# TSOC_RS485_EM.net
KiCad netlist of a schematic drawn in EAGLE
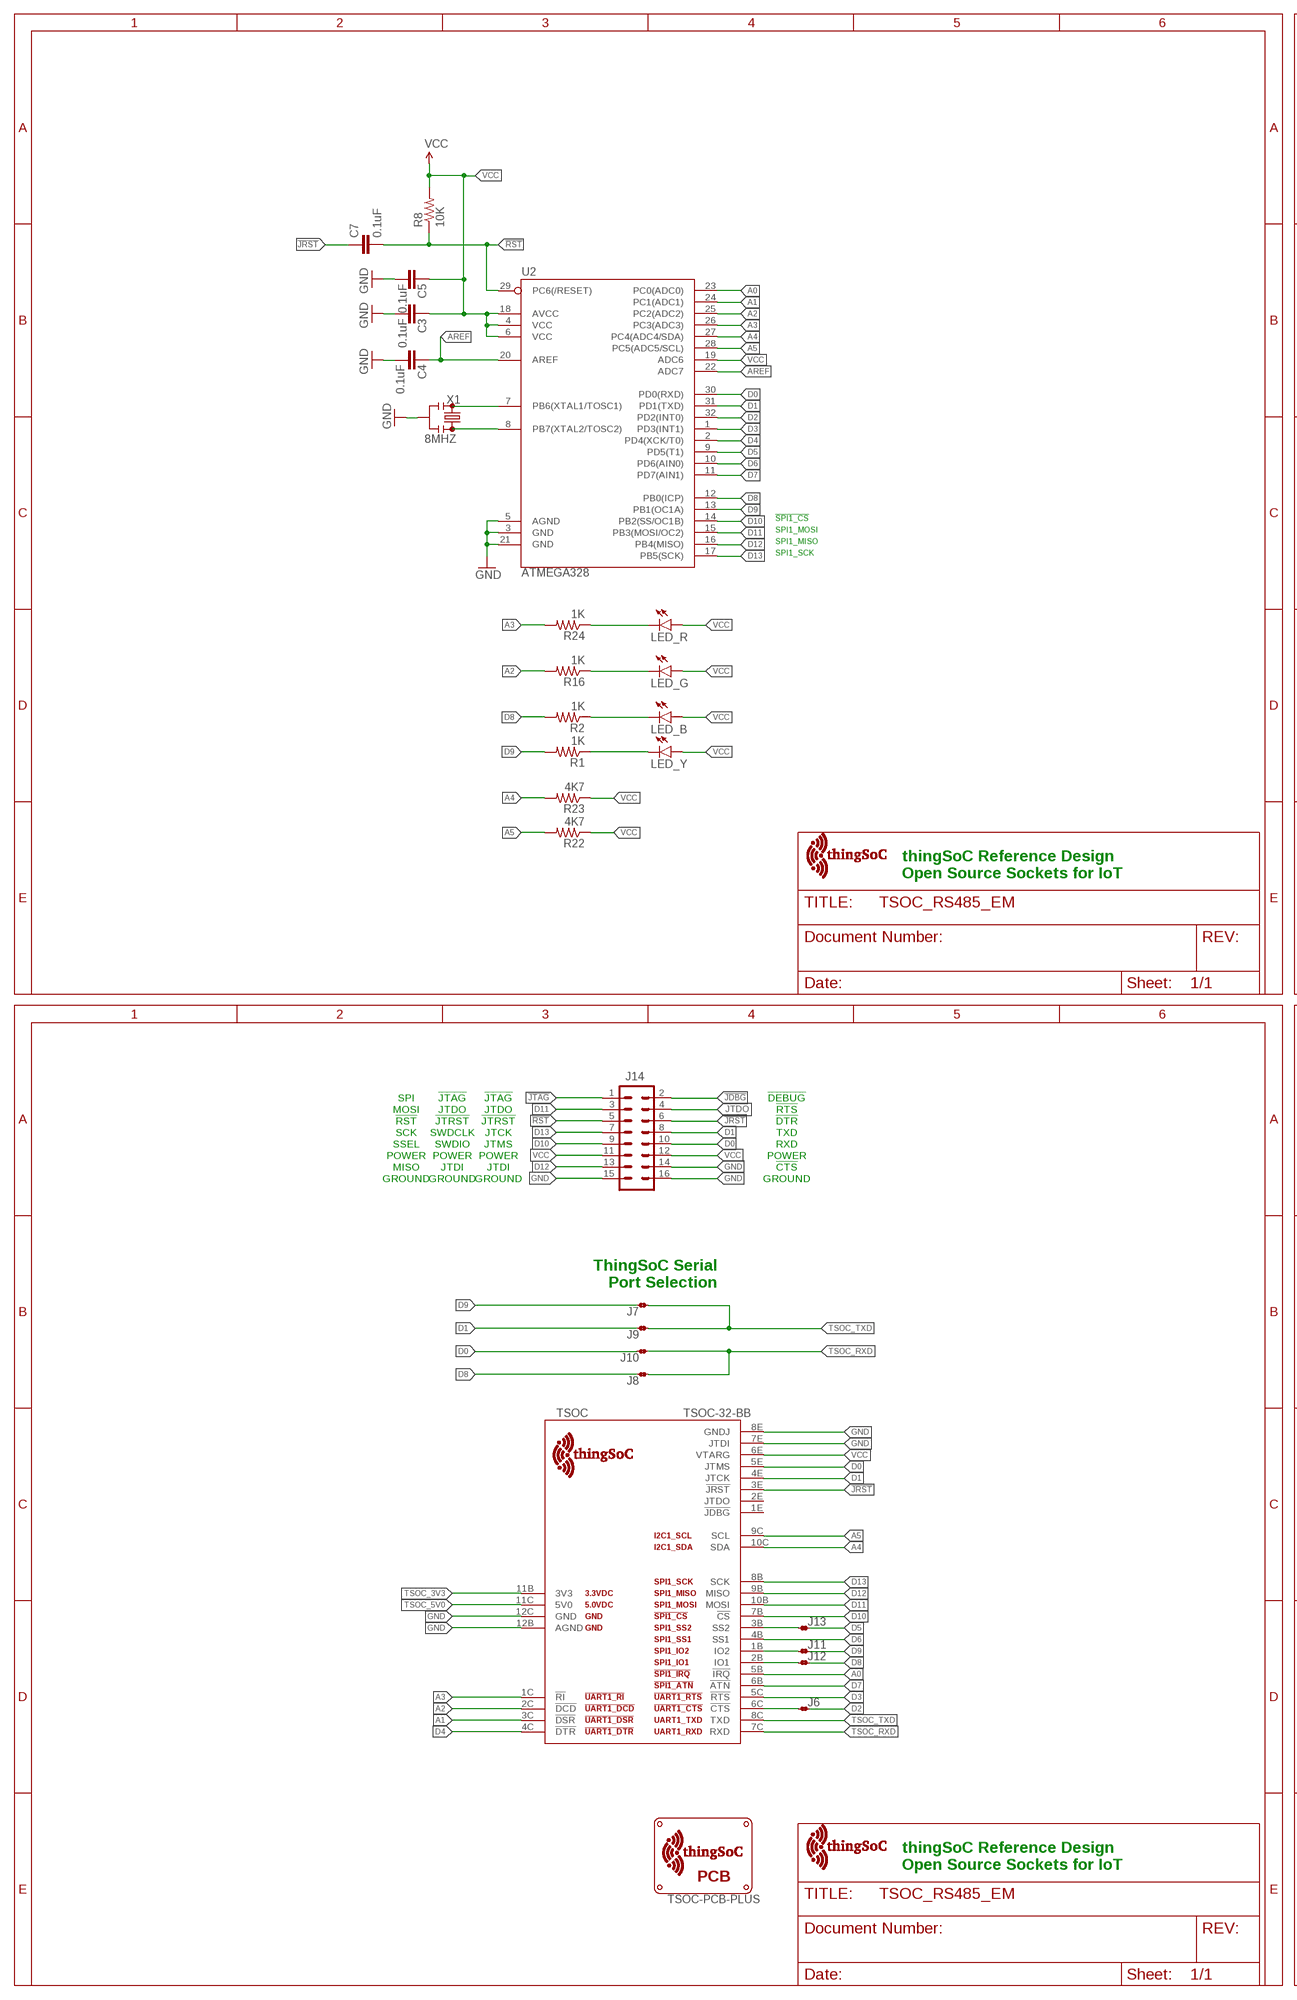
[diagram p0: schematic, sheet 1, part 1 of 2]
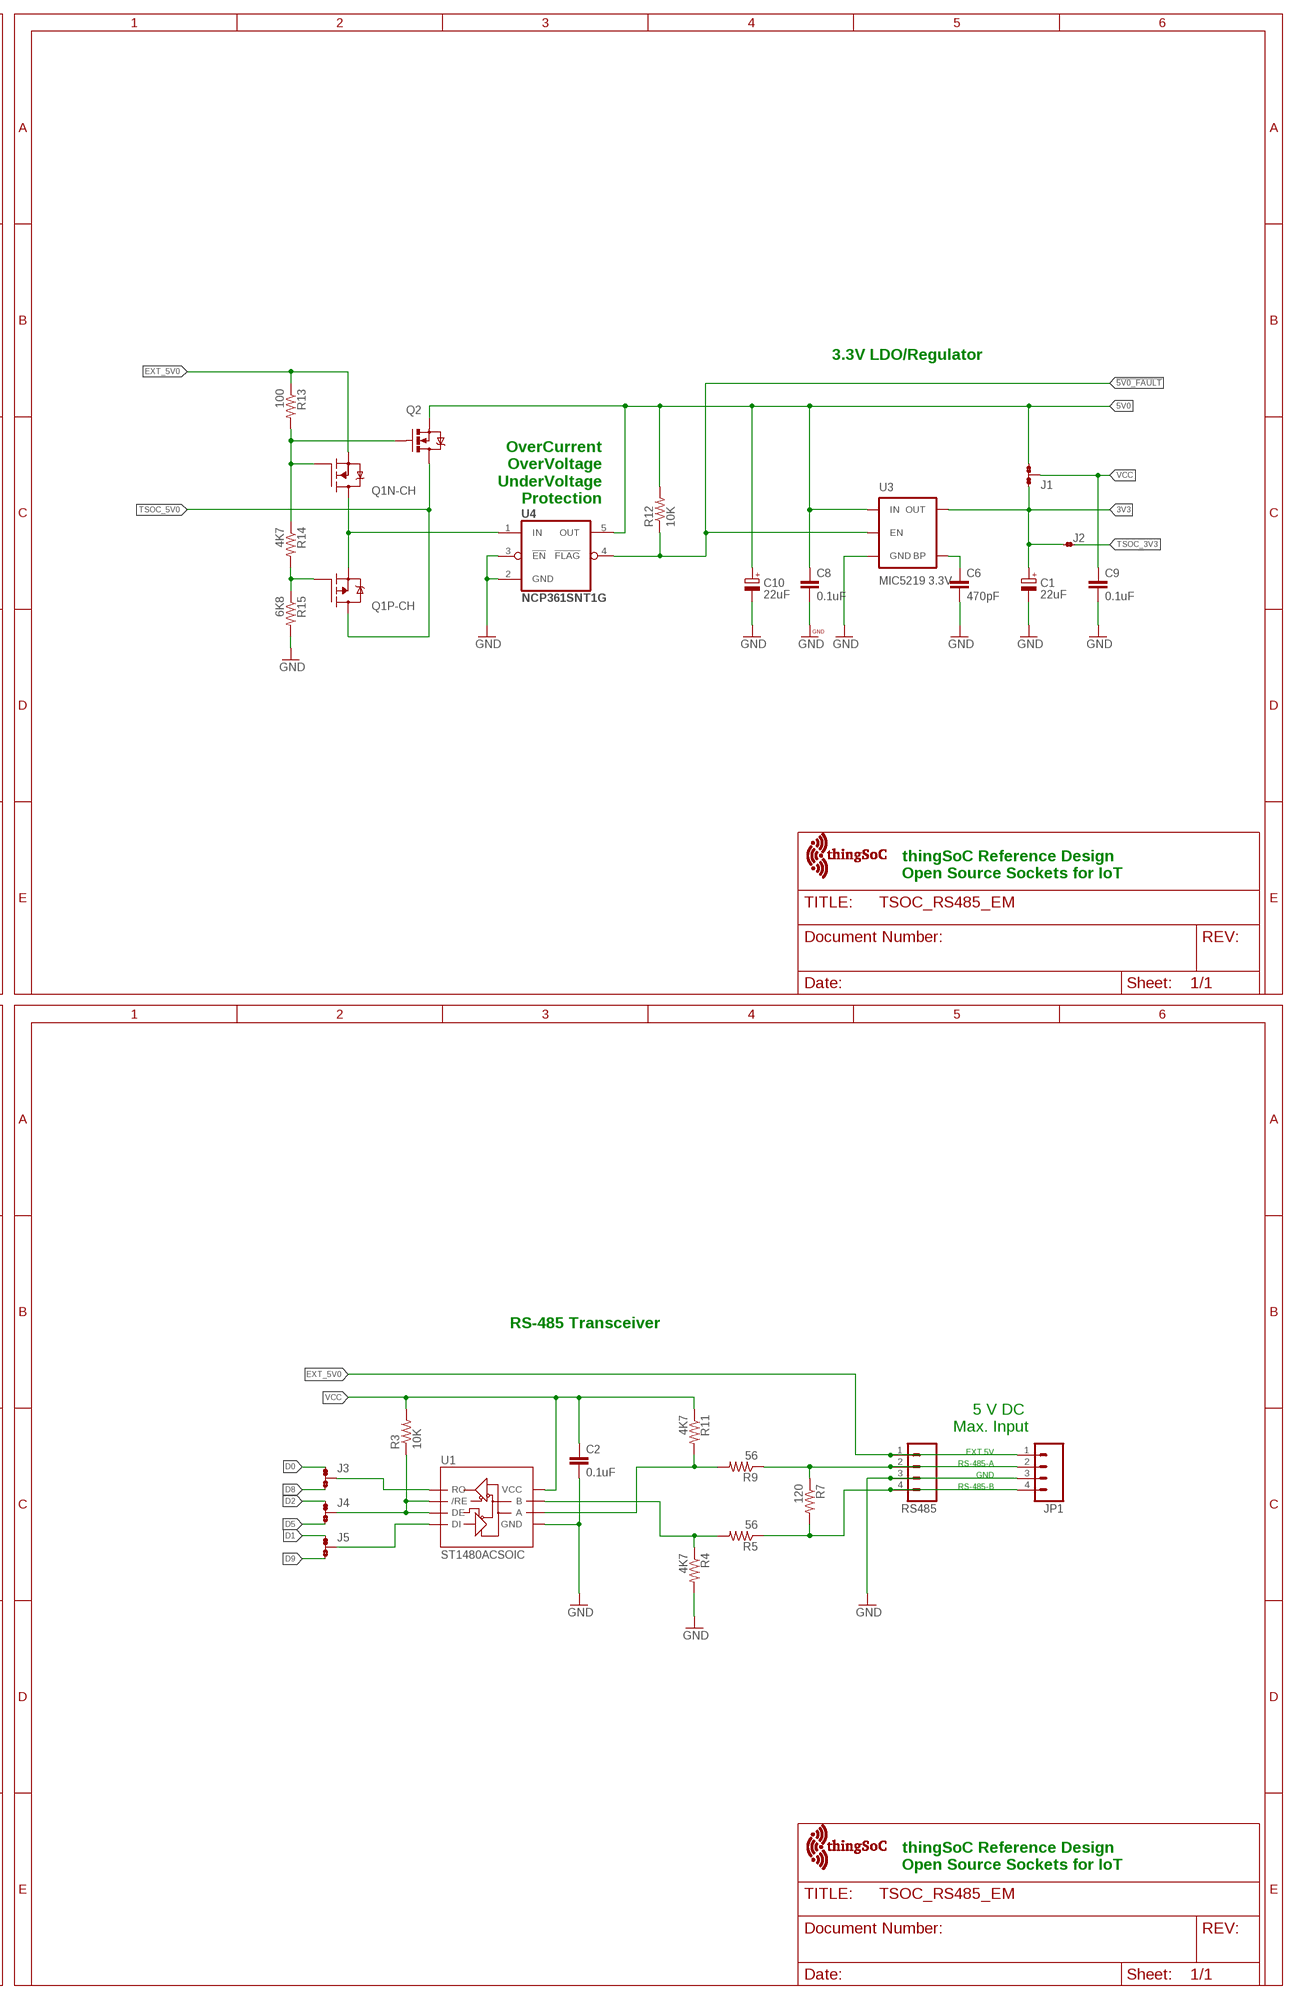
[diagram p1: schematic, sheet 1, part 2 of 2]

(export (version "E")
  (design (tool "Eeschema 10.0.6"))
  (components
    (comp (ref "C1")
      (value "22uF")
      (footprint "eagle-import:SMC_B")
      (libsource (lib "eagle-import") (part "CPOL-EUSMCB"))
    )
    (comp (ref "C2")
      (value "0.1uF")
      (footprint "eagle-import:EIA-0402")
      (libsource (lib "eagle-import") (part "CAPTYP"))
    )
    (comp (ref "C3")
      (value "0.1uF")
      (footprint "eagle-import:EIA-0402")
      (libsource (lib "eagle-import") (part "CAPTYP"))
    )
    (comp (ref "C4")
      (value "0.1uF")
      (footprint "eagle-import:EIA-0402")
      (libsource (lib "eagle-import") (part "CAPTYP"))
    )
    (comp (ref "C5")
      (value "0.1uF")
      (footprint "eagle-import:EIA-0402")
      (libsource (lib "eagle-import") (part "CAPTYP"))
    )
    (comp (ref "C6")
      (value "470pF")
      (footprint "eagle-import:EIA-0402")
      (libsource (lib "eagle-import") (part "CAPTYP"))
    )
    (comp (ref "C7")
      (value "0.1uF")
      (footprint "eagle-import:EIA-0402")
      (libsource (lib "eagle-import") (part "CAPTYP"))
    )
    (comp (ref "C8")
      (value "0.1uF")
      (footprint "eagle-import:EIA-0402")
      (libsource (lib "eagle-import") (part "CAPTYP"))
    )
    (comp (ref "C9")
      (value "0.1uF")
      (footprint "eagle-import:EIA-0402")
      (libsource (lib "eagle-import") (part "CAPTYP"))
    )
    (comp (ref "C10")
      (value "22uF")
      (footprint "eagle-import:SMC_B")
      (libsource (lib "eagle-import") (part "CPOL-EUSMCB"))
    )
    (comp (ref "J1")
      (value "JMP-3-1_2")
      (footprint "eagle-import:JMP-3-1_2")
      (libsource (lib "eagle-import") (part "JMP-3-1_2"))
    )
    (comp (ref "J2")
      (value "JMP-2-NC")
      (footprint "eagle-import:JMP-2-NC")
      (libsource (lib "eagle-import") (part "JMP-2-NC"))
    )
    (comp (ref "J3")
      (value "JMP-3-1_2")
      (footprint "eagle-import:JMP-3-1_2")
      (libsource (lib "eagle-import") (part "TSOC_RS485_EM_JMP-3-1_2"))
    )
    (comp (ref "J4")
      (value "JMP-3-1_2")
      (footprint "eagle-import:JMP-3-1_2")
      (libsource (lib "eagle-import") (part "TSOC_RS485_EM_JMP-3-1_2"))
    )
    (comp (ref "J5")
      (value "JMP-3-1_2")
      (footprint "eagle-import:JMP-3-1_2")
      (libsource (lib "eagle-import") (part "TSOC_RS485_EM_JMP-3-1_2"))
    )
    (comp (ref "J6")
      (value "JMP-2-NO")
      (footprint "eagle-import:JMP-2-NO")
      (libsource (lib "eagle-import") (part "JMP-2-NO"))
    )
    (comp (ref "J7")
      (value "JMP-2-NO")
      (footprint "eagle-import:JMP-2-NO")
      (libsource (lib "eagle-import") (part "JMP-2-NO"))
    )
    (comp (ref "J8")
      (value "JMP-2-NO")
      (footprint "eagle-import:JMP-2-NO")
      (libsource (lib "eagle-import") (part "JMP-2-NO"))
    )
    (comp (ref "J9")
      (value "JMP-2-NO")
      (footprint "eagle-import:JMP-2-NO")
      (libsource (lib "eagle-import") (part "JMP-2-NO"))
    )
    (comp (ref "J10")
      (value "JMP-2-NO")
      (footprint "eagle-import:JMP-2-NO")
      (libsource (lib "eagle-import") (part "JMP-2-NO"))
    )
    (comp (ref "J11")
      (value "JMP-2-NC")
      (footprint "eagle-import:JMP-2-NC")
      (libsource (lib "eagle-import") (part "JMP-2-NC"))
    )
    (comp (ref "J12")
      (value "JMP-2-NC")
      (footprint "eagle-import:JMP-2-NC")
      (libsource (lib "eagle-import") (part "JMP-2-NC"))
    )
    (comp (ref "J13")
      (value "JMP-2-NC")
      (footprint "eagle-import:JMP-2-NC")
      (libsource (lib "eagle-import") (part "JMP-2-NC"))
    )
    (comp (ref "J14")
      (value "M08X2")
      (footprint "eagle-import:2X8")
      (libsource (lib "eagle-import") (part "M08X2"))
    )
    (comp (ref "JP1")
      (value "M04PTH")
      (footprint "eagle-import:1X04")
      (libsource (lib "eagle-import") (part "M04PTH"))
    )
    (comp (ref "LED_B")
      (value "LED0603")
      (footprint "eagle-import:LED-0603")
      (libsource (lib "eagle-import") (part "LED0603"))
    )
    (comp (ref "LED_G")
      (value "LED0603")
      (footprint "eagle-import:LED-0603")
      (libsource (lib "eagle-import") (part "LED0603"))
    )
    (comp (ref "LED_R")
      (value "LED0603")
      (footprint "eagle-import:LED-0603")
      (libsource (lib "eagle-import") (part "LED0603"))
    )
    (comp (ref "LED_Y")
      (value "LED0603")
      (footprint "eagle-import:LED-0603")
      (libsource (lib "eagle-import") (part "LED0603"))
    )
    (comp (ref "Q1")
      (value "FDC6420C")
      (footprint "eagle-import:SOT95P280X110-6N")
      (libsource (lib "eagle-import") (part "FDC6420C"))
    )
    (comp (ref "Q2")
      (value "MOSFET-NCHANNELAO3404A")
      (footprint "eagle-import:SOT23-3")
      (libsource (lib "eagle-import") (part "MOSFET-NCHANNELAO3404A"))
    )
    (comp (ref "R1")
      (value "1K")
      (footprint "eagle-import:EIA-0402-MIN")
      (libsource (lib "eagle-import") (part "RESISTOR0402-MIN"))
    )
    (comp (ref "R2")
      (value "1K")
      (footprint "eagle-import:EIA-0402-MIN")
      (libsource (lib "eagle-import") (part "RESISTOR0402-MIN"))
    )
    (comp (ref "R3")
      (value "10K")
      (footprint "eagle-import:EIA-0402-MIN")
      (libsource (lib "eagle-import") (part "RESISTOR0402-MIN"))
    )
    (comp (ref "R4")
      (value "4K7")
      (footprint "eagle-import:EIA-0402-MIN")
      (libsource (lib "eagle-import") (part "RESISTOR0402-MIN"))
    )
    (comp (ref "R5")
      (value "56")
      (footprint "eagle-import:EIA-0402-MIN")
      (libsource (lib "eagle-import") (part "RESISTOR0402-MIN"))
    )
    (comp (ref "R7")
      (value "120")
      (footprint "eagle-import:EIA-0402-MIN")
      (libsource (lib "eagle-import") (part "RESISTOR0402-MIN"))
    )
    (comp (ref "R8")
      (value "10K")
      (footprint "eagle-import:EIA-0402-MIN")
      (libsource (lib "eagle-import") (part "RESISTOR0402-MIN"))
    )
    (comp (ref "R9")
      (value "56")
      (footprint "eagle-import:EIA-0402-MIN")
      (libsource (lib "eagle-import") (part "RESISTOR0402-MIN"))
    )
    (comp (ref "R11")
      (value "4K7")
      (footprint "eagle-import:EIA-0402-MIN")
      (libsource (lib "eagle-import") (part "RESISTOR0402-MIN"))
    )
    (comp (ref "R12")
      (value "10K")
      (footprint "eagle-import:EIA-0402-MIN")
      (libsource (lib "eagle-import") (part "RESISTOR0402-MIN"))
    )
    (comp (ref "R13")
      (value "100")
      (footprint "eagle-import:EIA-0402-MIN")
      (libsource (lib "eagle-import") (part "RESISTOR0402-MIN"))
    )
    (comp (ref "R14")
      (value "4K7")
      (footprint "eagle-import:EIA-0402-MIN")
      (libsource (lib "eagle-import") (part "RESISTOR0402-MIN"))
    )
    (comp (ref "R15")
      (value "6K8")
      (footprint "eagle-import:EIA-0402-MIN")
      (libsource (lib "eagle-import") (part "RESISTOR0402-MIN"))
    )
    (comp (ref "R16")
      (value "1K")
      (footprint "eagle-import:EIA-0402-MIN")
      (libsource (lib "eagle-import") (part "RESISTOR0402-MIN"))
    )
    (comp (ref "R22")
      (value "4K7")
      (footprint "eagle-import:EIA-0402-MIN")
      (libsource (lib "eagle-import") (part "RESISTOR0402-MIN"))
    )
    (comp (ref "R23")
      (value "4K7")
      (footprint "eagle-import:EIA-0402-MIN")
      (libsource (lib "eagle-import") (part "RESISTOR0402-MIN"))
    )
    (comp (ref "R24")
      (value "1K")
      (footprint "eagle-import:EIA-0402-MIN")
      (libsource (lib "eagle-import") (part "RESISTOR0402-MIN"))
    )
    (comp (ref "RS485")
      (value "M04SCREW")
      (footprint "eagle-import:SCREWTERMINAL-3.5MM-4")
      (libsource (lib "eagle-import") (part "M04SCREW"))
    )
    (comp (ref "TSOC")
      (value "TSOC-32-BB")
      (footprint "eagle-import:TSOC-BB-S32")
      (libsource (lib "eagle-import") (part "TSOC-32-BB"))
    )
    (comp (ref "U$3")
      (value "TSOC-PCB-PLUS")
      (footprint "eagle-import:TSOC-BB-BRD-PLUS")
      (libsource (lib "eagle-import") (part "TSOC-PCB-PLUS"))
    )
    (comp (ref "U$5")
      (value "TSOC-LOGO-SMALL")
      (footprint "eagle-import:TSOC-LOGO-SML")
      (libsource (lib "eagle-import") (part "TSOC-LOGO-SMALL"))
    )
    (comp (ref "U$6")
      (value "TSOC-LOGO-SMALL")
      (footprint "eagle-import:TSOC-LOGO-SML")
      (libsource (lib "eagle-import") (part "TSOC-LOGO-SMALL"))
    )
    (comp (ref "U$7")
      (value "TSOC-LOGO-SMALL")
      (footprint "eagle-import:TSOC-LOGO-SML")
      (libsource (lib "eagle-import") (part "TSOC-LOGO-SMALL"))
    )
    (comp (ref "U$8")
      (value "TSOC-LOGO-SMALL")
      (footprint "eagle-import:TSOC-LOGO-SML")
      (libsource (lib "eagle-import") (part "TSOC-LOGO-SMALL"))
    )
    (comp (ref "U1")
      (value "ST1480ACSOIC")
      (footprint "eagle-import:SO08")
      (libsource (lib "eagle-import") (part "ST1480ACSOIC"))
    )
    (comp (ref "U2")
      (value "ATMEGA328")
      (footprint "eagle-import:TQFP32-08")
      (libsource (lib "eagle-import") (part "ATMEGA168"))
    )
    (comp (ref "U3")
      (value "MIC5219 3.3V")
      (footprint "eagle-import:SOT23-5")
      (libsource (lib "eagle-import") (part "V_REG_MIC52193.3V"))
    )
    (comp (ref "U4")
      (value "NCP361SNT1G")
      (footprint "eagle-import:SOP95P275X110-5N")
      (libsource (lib "eagle-import") (part "NCP361SNT1G"))
    )
    (comp (ref "X1")
      (value "8MHZ")
      (footprint "eagle-import:RESONATOR-SMD")
      (libsource (lib "eagle-import") (part "RESONATOR8MHZ"))
    )
  )
  (nets
    (net (code "1") (name "/~{5V0_FAULT}") (class "Default")
      (node (ref "R12") (pin "1") (pinfunction "1_1") (pintype "passive"))
      (node (ref "U3") (pin "3") (pinfunction "EN_3") (pintype "input"))
      (node (ref "U4") (pin "4") (pinfunction "~{FLAG}_4") (pintype "input"))
    )
    (net (code "2") (name "/~{JDBG}") (class "Default")
      (node (ref "J14") (pin "2") (pinfunction "2_2") (pintype "passive"))
    )
    (net (code "3") (name "/~{JRST}") (class "Default")
      (node (ref "C7") (pin "1") (pinfunction "1_1") (pintype "passive"))
      (node (ref "J14") (pin "6") (pinfunction "6_6") (pintype "passive"))
      (node (ref "TSOC") (pin "3E") (pinfunction "~{JRST}_3E") (pintype "bidirectional"))
    )
    (net (code "4") (name "/~{JTAG}") (class "Default")
      (node (ref "J14") (pin "1") (pinfunction "1_1") (pintype "passive"))
    )
    (net (code "5") (name "/~{RST}") (class "Default")
      (node (ref "C7") (pin "2") (pinfunction "2_2") (pintype "passive"))
      (node (ref "J14") (pin "5") (pinfunction "5_5") (pintype "passive"))
      (node (ref "R8") (pin "1") (pinfunction "1_1") (pintype "passive"))
      (node (ref "U2") (pin "29") (pinfunction "PC6(/RESET)_29") (pintype "bidirectional"))
    )
    (net (code "6") (name "3V3") (class "Default")
      (node (ref "C1") (pin "+") (pinfunction "+_+") (pintype "passive"))
      (node (ref "J1") (pin "1") (pinfunction "1_1") (pintype "passive"))
      (node (ref "J2") (pin "1") (pinfunction "1_1") (pintype "passive"))
      (node (ref "U3") (pin "5") (pinfunction "OUT_5") (pintype "passive"))
    )
    (net (code "7") (name "5V0") (class "Default")
      (node (ref "C10") (pin "+") (pinfunction "+_+") (pintype "passive"))
      (node (ref "C8") (pin "1") (pinfunction "1_1") (pintype "passive"))
      (node (ref "J1") (pin "3") (pinfunction "3_3") (pintype "passive"))
      (node (ref "Q2") (pin "2") (pinfunction "S_2") (pintype "passive"))
      (node (ref "R12") (pin "2") (pinfunction "2_2") (pintype "passive"))
      (node (ref "U3") (pin "1") (pinfunction "IN_1") (pintype "input"))
      (node (ref "U4") (pin "5") (pinfunction "OUT_5") (pintype "output"))
    )
    (net (code "8") (name "A0") (class "Default")
      (node (ref "TSOC") (pin "5B") (pinfunction "~{IRQ}_5B") (pintype "bidirectional"))
      (node (ref "U2") (pin "23") (pinfunction "PC0(ADC0)_23") (pintype "bidirectional"))
    )
    (net (code "9") (name "A1") (class "Default")
      (node (ref "TSOC") (pin "3C") (pinfunction "~{DSR}_3C") (pintype "bidirectional"))
      (node (ref "U2") (pin "24") (pinfunction "PC1(ADC1)_24") (pintype "bidirectional"))
    )
    (net (code "10") (name "A2") (class "Default")
      (node (ref "R16") (pin "2") (pinfunction "2_2") (pintype "passive"))
      (node (ref "TSOC") (pin "2C") (pinfunction "~{DCD}_2C") (pintype "bidirectional"))
      (node (ref "U2") (pin "25") (pinfunction "PC2(ADC2)_25") (pintype "bidirectional"))
    )
    (net (code "11") (name "A3") (class "Default")
      (node (ref "R24") (pin "2") (pinfunction "2_2") (pintype "passive"))
      (node (ref "TSOC") (pin "1C") (pinfunction "~{RI}_1C") (pintype "bidirectional"))
      (node (ref "U2") (pin "26") (pinfunction "PC3(ADC3)_26") (pintype "bidirectional"))
    )
    (net (code "12") (name "A4") (class "Default")
      (node (ref "R23") (pin "2") (pinfunction "2_2") (pintype "passive"))
      (node (ref "TSOC") (pin "10C") (pinfunction "SDA_10C") (pintype "bidirectional"))
      (node (ref "U2") (pin "27") (pinfunction "PC4(ADC4/SDA)_27") (pintype "bidirectional"))
    )
    (net (code "13") (name "A5") (class "Default")
      (node (ref "R22") (pin "2") (pinfunction "2_2") (pintype "passive"))
      (node (ref "TSOC") (pin "9C") (pinfunction "SCL_9C") (pintype "bidirectional"))
      (node (ref "U2") (pin "28") (pinfunction "PC5(ADC5/SCL)_28") (pintype "bidirectional"))
    )
    (net (code "14") (name "AREF") (class "Default")
      (node (ref "C4") (pin "2") (pinfunction "2_2") (pintype "passive"))
      (node (ref "U2") (pin "20") (pinfunction "AREF_20") (pintype "bidirectional"))
      (node (ref "U2") (pin "22") (pinfunction "ADC7_22") (pintype "bidirectional"))
    )
    (net (code "15") (name "D0") (class "Default")
      (node (ref "J10") (pin "2") (pinfunction "2_2") (pintype "passive"))
      (node (ref "J14") (pin "10") (pinfunction "10_10") (pintype "passive"))
      (node (ref "J3") (pin "1") (pinfunction "1_1") (pintype "passive"))
      (node (ref "TSOC") (pin "5E") (pinfunction "JTMS_5E") (pintype "bidirectional"))
      (node (ref "U2") (pin "30") (pinfunction "PD0(RXD)_30") (pintype "bidirectional"))
    )
    (net (code "16") (name "D1") (class "Default")
      (node (ref "J14") (pin "8") (pinfunction "8_8") (pintype "passive"))
      (node (ref "J5") (pin "1") (pinfunction "1_1") (pintype "passive"))
      (node (ref "J9") (pin "2") (pinfunction "2_2") (pintype "passive"))
      (node (ref "TSOC") (pin "4E") (pinfunction "JTCK_4E") (pintype "bidirectional"))
      (node (ref "U2") (pin "31") (pinfunction "PD1(TXD)_31") (pintype "bidirectional"))
    )
    (net (code "17") (name "D2") (class "Default")
      (node (ref "J4") (pin "1") (pinfunction "1_1") (pintype "passive"))
      (node (ref "J6") (pin "2") (pinfunction "2_2") (pintype "passive"))
      (node (ref "U2") (pin "32") (pinfunction "PD2(INT0)_32") (pintype "bidirectional"))
    )
    (net (code "18") (name "D3") (class "Default")
      (node (ref "TSOC") (pin "5C") (pinfunction "~{RTS}_5C") (pintype "bidirectional"))
      (node (ref "U2") (pin "1") (pinfunction "PD3(INT1)_1") (pintype "bidirectional"))
    )
    (net (code "19") (name "D4") (class "Default")
      (node (ref "TSOC") (pin "4C") (pinfunction "~{DTR}_4C") (pintype "bidirectional"))
      (node (ref "U2") (pin "2") (pinfunction "PD4(XCK/T0)_2") (pintype "bidirectional"))
    )
    (net (code "20") (name "D5") (class "Default")
      (node (ref "J13") (pin "2") (pinfunction "2_2") (pintype "passive"))
      (node (ref "J4") (pin "3") (pinfunction "3_3") (pintype "passive"))
      (node (ref "U2") (pin "9") (pinfunction "PD5(T1)_9") (pintype "bidirectional"))
    )
    (net (code "21") (name "D6") (class "Default")
      (node (ref "TSOC") (pin "4B") (pinfunction "SS1_4B") (pintype "bidirectional"))
      (node (ref "U2") (pin "10") (pinfunction "PD6(AIN0)_10") (pintype "bidirectional"))
    )
    (net (code "22") (name "D7") (class "Default")
      (node (ref "TSOC") (pin "6B") (pinfunction "~{ATN}_6B") (pintype "bidirectional"))
      (node (ref "U2") (pin "11") (pinfunction "PD7(AIN1)_11") (pintype "bidirectional"))
    )
    (net (code "23") (name "D8") (class "Default")
      (node (ref "J12") (pin "2") (pinfunction "2_2") (pintype "passive"))
      (node (ref "J3") (pin "3") (pinfunction "3_3") (pintype "passive"))
      (node (ref "J8") (pin "2") (pinfunction "2_2") (pintype "passive"))
      (node (ref "R2") (pin "2") (pinfunction "2_2") (pintype "passive"))
      (node (ref "U2") (pin "12") (pinfunction "PB0(ICP)_12") (pintype "bidirectional"))
    )
    (net (code "24") (name "D9") (class "Default")
      (node (ref "J11") (pin "2") (pinfunction "2_2") (pintype "passive"))
      (node (ref "J5") (pin "3") (pinfunction "3_3") (pintype "passive"))
      (node (ref "J7") (pin "2") (pinfunction "2_2") (pintype "passive"))
      (node (ref "R1") (pin "2") (pinfunction "2_2") (pintype "passive"))
      (node (ref "U2") (pin "13") (pinfunction "PB1(OC1A)_13") (pintype "bidirectional"))
    )
    (net (code "25") (name "D10") (class "Default")
      (node (ref "J14") (pin "9") (pinfunction "9_9") (pintype "passive"))
      (node (ref "TSOC") (pin "7B") (pinfunction "~{CS}_7B") (pintype "bidirectional"))
      (node (ref "U2") (pin "14") (pinfunction "PB2(SS/OC1B)_14") (pintype "bidirectional"))
    )
    (net (code "26") (name "D11") (class "Default")
      (node (ref "J14") (pin "3") (pinfunction "3_3") (pintype "passive"))
      (node (ref "TSOC") (pin "10B") (pinfunction "MOSI_10B") (pintype "bidirectional"))
      (node (ref "U2") (pin "15") (pinfunction "PB3(MOSI/OC2)_15") (pintype "bidirectional"))
    )
    (net (code "27") (name "D12") (class "Default")
      (node (ref "J14") (pin "13") (pinfunction "13_13") (pintype "passive"))
      (node (ref "TSOC") (pin "9B") (pinfunction "MISO_9B") (pintype "bidirectional"))
      (node (ref "U2") (pin "16") (pinfunction "PB4(MISO)_16") (pintype "bidirectional"))
    )
    (net (code "28") (name "D13") (class "Default")
      (node (ref "J14") (pin "7") (pinfunction "7_7") (pintype "passive"))
      (node (ref "TSOC") (pin "8B") (pinfunction "SCK_8B") (pintype "bidirectional"))
      (node (ref "U2") (pin "17") (pinfunction "PB5(SCK)_17") (pintype "bidirectional"))
    )
    (net (code "29") (name "EXT_5V0") (class "Default")
      (node (ref "JP1") (pin "1") (pinfunction "1_1") (pintype "passive"))
      (node (ref "Q1") (pin "5") (pinfunction "S_5") (pintype "passive"))
      (node (ref "R13") (pin "1") (pinfunction "1_1") (pintype "passive"))
      (node (ref "RS485") (pin "1") (pinfunction "1_1") (pintype "passive"))
    )
    (net (code "30") (name "GND") (class "Default")
      (node (ref "C1") (pin "-") (pinfunction "-_-") (pintype "passive"))
      (node (ref "C10") (pin "-") (pinfunction "-_-") (pintype "passive"))
      (node (ref "C2") (pin "2") (pinfunction "2_2") (pintype "passive"))
      (node (ref "C3") (pin "1") (pinfunction "1_1") (pintype "passive"))
      (node (ref "C4") (pin "1") (pinfunction "1_1") (pintype "passive"))
      (node (ref "C5") (pin "1") (pinfunction "1_1") (pintype "passive"))
      (node (ref "C6") (pin "2") (pinfunction "2_2") (pintype "passive"))
      (node (ref "C8") (pin "2") (pinfunction "2_2") (pintype "passive"))
      (node (ref "C9") (pin "2") (pinfunction "2_2") (pintype "passive"))
      (node (ref "J14") (pin "14") (pinfunction "14_14") (pintype "passive"))
      (node (ref "J14") (pin "15") (pinfunction "15_15") (pintype "passive"))
      (node (ref "J14") (pin "16") (pinfunction "16_16") (pintype "passive"))
      (node (ref "JP1") (pin "3") (pinfunction "3_3") (pintype "passive"))
      (node (ref "R15") (pin "2") (pinfunction "2_2") (pintype "passive"))
      (node (ref "R4") (pin "2") (pinfunction "2_2") (pintype "passive"))
      (node (ref "RS485") (pin "3") (pinfunction "3_3") (pintype "passive"))
      (node (ref "TSOC") (pin "12B") (pinfunction "AGND_12B") (pintype "bidirectional"))
      (node (ref "TSOC") (pin "12C") (pinfunction "GND_12C") (pintype "bidirectional"))
      (node (ref "TSOC") (pin "7E") (pinfunction "JTDI_7E") (pintype "bidirectional"))
      (node (ref "TSOC") (pin "8E") (pinfunction "GNDJ_8E") (pintype "bidirectional"))
      (node (ref "U1") (pin "5") (pinfunction "GND_5") (pintype "bidirectional"))
      (node (ref "U2") (pin "21") (pinfunction "GND_21") (pintype "bidirectional"))
      (node (ref "U2") (pin "3") (pinfunction "GND_3") (pintype "bidirectional"))
      (node (ref "U2") (pin "5") (pinfunction "AGND_5") (pintype "bidirectional"))
      (node (ref "U3") (pin "2") (pinfunction "GND_2") (pintype "input"))
      (node (ref "U4") (pin "2") (pinfunction "GND_2") (pintype "passive"))
      (node (ref "U4") (pin "3") (pinfunction "~{EN}_3") (pintype "input"))
      (node (ref "X1") (pin "2") (pinfunction "2_2") (pintype "passive"))
    )
    (net (code "31") (name "JTDO") (class "Default")
      (node (ref "J14") (pin "4") (pinfunction "4_4") (pintype "passive"))
    )
    (net (code "32") (name "Net-(JP1-Pad2)") (class "Default")
      (node (ref "JP1") (pin "2") (pinfunction "2_2") (pintype "passive"))
      (node (ref "R7") (pin "1") (pinfunction "1_1") (pintype "passive"))
      (node (ref "R9") (pin "1") (pinfunction "1_1") (pintype "passive"))
      (node (ref "RS485") (pin "2") (pinfunction "2_2") (pintype "passive"))
    )
    (net (code "33") (name "Net-(JP1-Pad4)") (class "Default")
      (node (ref "JP1") (pin "4") (pinfunction "4_4") (pintype "passive"))
      (node (ref "R5") (pin "1") (pinfunction "1_1") (pintype "passive"))
      (node (ref "R7") (pin "2") (pinfunction "2_2") (pintype "passive"))
      (node (ref "RS485") (pin "4") (pinfunction "4_4") (pintype "passive"))
    )
    (net (code "34") (name "Net-(LED_B-PadC)") (class "Default")
      (node (ref "LED_B") (pin "C") (pinfunction "C_C") (pintype "passive"))
      (node (ref "R2") (pin "1") (pinfunction "1_1") (pintype "passive"))
    )
    (net (code "35") (name "Net-(LED_G-PadC)") (class "Default")
      (node (ref "LED_G") (pin "C") (pinfunction "C_C") (pintype "passive"))
      (node (ref "R16") (pin "1") (pinfunction "1_1") (pintype "passive"))
    )
    (net (code "36") (name "Net-(LED_R-PadC)") (class "Default")
      (node (ref "LED_R") (pin "C") (pinfunction "C_C") (pintype "passive"))
      (node (ref "R24") (pin "1") (pinfunction "1_1") (pintype "passive"))
    )
    (net (code "37") (name "Net-(LED_Y-PadC)") (class "Default")
      (node (ref "LED_Y") (pin "C") (pinfunction "C_C") (pintype "passive"))
      (node (ref "R1") (pin "1") (pinfunction "1_1") (pintype "passive"))
    )
    (net (code "38") (name "Net-(Q1A-D)") (class "Default")
      (node (ref "Q1") (pin "2") (pinfunction "S_2") (pintype "passive"))
      (node (ref "Q1") (pin "6") (pinfunction "D_6") (pintype "passive"))
      (node (ref "U4") (pin "1") (pinfunction "IN_1") (pintype "power_in"))
    )
    (net (code "39") (name "Net-(Q1A-G)") (class "Default")
      (node (ref "Q1") (pin "1") (pinfunction "G_1") (pintype "passive"))
      (node (ref "Q2") (pin "1") (pinfunction "G_1") (pintype "passive"))
      (node (ref "R13") (pin "2") (pinfunction "2_2") (pintype "passive"))
      (node (ref "R14") (pin "1") (pinfunction "1_1") (pintype "passive"))
    )
    (net (code "40") (name "Net-(Q1B-G)") (class "Default")
      (node (ref "Q1") (pin "3") (pinfunction "G_3") (pintype "passive"))
      (node (ref "R14") (pin "2") (pinfunction "2_2") (pintype "passive"))
      (node (ref "R15") (pin "1") (pinfunction "1_1") (pintype "passive"))
    )
    (net (code "41") (name "Net-(TSOC-IO1)") (class "Default")
      (node (ref "J12") (pin "1") (pinfunction "1_1") (pintype "passive"))
      (node (ref "TSOC") (pin "2B") (pinfunction "IO1_2B") (pintype "bidirectional"))
    )
    (net (code "42") (name "Net-(TSOC-IO2)") (class "Default")
      (node (ref "J11") (pin "1") (pinfunction "1_1") (pintype "passive"))
      (node (ref "TSOC") (pin "1B") (pinfunction "IO2_1B") (pintype "bidirectional"))
    )
    (net (code "43") (name "Net-(TSOC-SS2)") (class "Default")
      (node (ref "J13") (pin "1") (pinfunction "1_1") (pintype "passive"))
      (node (ref "TSOC") (pin "3B") (pinfunction "SS2_3B") (pintype "bidirectional"))
    )
    (net (code "44") (name "Net-(TSOC-~{CTS})") (class "Default")
      (node (ref "J6") (pin "1") (pinfunction "1_1") (pintype "passive"))
      (node (ref "TSOC") (pin "6C") (pinfunction "~{CTS}_6C") (pintype "bidirectional"))
    )
    (net (code "45") (name "Net-(U1-A)") (class "Default")
      (node (ref "R11") (pin "2") (pinfunction "2_2") (pintype "passive"))
      (node (ref "R9") (pin "2") (pinfunction "2_2") (pintype "passive"))
      (node (ref "U1") (pin "6") (pinfunction "A_6") (pintype "bidirectional"))
    )
    (net (code "46") (name "Net-(U1-B)") (class "Default")
      (node (ref "R4") (pin "1") (pinfunction "1_1") (pintype "passive"))
      (node (ref "R5") (pin "2") (pinfunction "2_2") (pintype "passive"))
      (node (ref "U1") (pin "7") (pinfunction "B_7") (pintype "bidirectional"))
    )
    (net (code "47") (name "Net-(U1-DE)") (class "Default")
      (node (ref "J4") (pin "2") (pinfunction "2_2") (pintype "passive"))
      (node (ref "R3") (pin "1") (pinfunction "1_1") (pintype "passive"))
      (node (ref "U1") (pin "2") (pinfunction "/RE_2") (pintype "bidirectional"))
      (node (ref "U1") (pin "3") (pinfunction "DE_3") (pintype "bidirectional"))
    )
    (net (code "48") (name "Net-(U1-DI)") (class "Default")
      (node (ref "J5") (pin "2") (pinfunction "2_2") (pintype "passive"))
      (node (ref "U1") (pin "4") (pinfunction "DI_4") (pintype "bidirectional"))
    )
    (net (code "49") (name "Net-(U1-RO)") (class "Default")
      (node (ref "J3") (pin "2") (pinfunction "2_2") (pintype "passive"))
      (node (ref "U1") (pin "1") (pinfunction "RO_1") (pintype "bidirectional"))
    )
    (net (code "50") (name "Net-(U2-PB6(XTAL1{slash}TOSC1))") (class "Default")
      (node (ref "U2") (pin "7") (pinfunction "PB6(XTAL1/TOSC1)_7") (pintype "bidirectional"))
      (node (ref "X1") (pin "3") (pinfunction "3_3") (pintype "passive"))
    )
    (net (code "51") (name "Net-(U2-PB7(XTAL2{slash}TOSC2))") (class "Default")
      (node (ref "U2") (pin "8") (pinfunction "PB7(XTAL2/TOSC2)_8") (pintype "bidirectional"))
      (node (ref "X1") (pin "1") (pinfunction "1_1") (pintype "passive"))
    )
    (net (code "52") (name "Net-(U3-BP)") (class "Default")
      (node (ref "C6") (pin "1") (pinfunction "1_1") (pintype "passive"))
      (node (ref "U3") (pin "4") (pinfunction "BP_4") (pintype "input"))
    )
    (net (code "53") (name "TSOC_3V3") (class "Default")
      (node (ref "J2") (pin "2") (pinfunction "2_2") (pintype "passive"))
      (node (ref "TSOC") (pin "11B") (pinfunction "3V3_11B") (pintype "bidirectional"))
    )
    (net (code "54") (name "TSOC_5V0") (class "Default")
      (node (ref "Q1") (pin "4") (pinfunction "D_4") (pintype "passive"))
      (node (ref "Q2") (pin "3") (pinfunction "D_3") (pintype "passive"))
      (node (ref "TSOC") (pin "11C") (pinfunction "5V0_11C") (pintype "bidirectional"))
    )
    (net (code "55") (name "TSOC_RXD") (class "Default")
      (node (ref "J10") (pin "1") (pinfunction "1_1") (pintype "passive"))
      (node (ref "J8") (pin "1") (pinfunction "1_1") (pintype "passive"))
      (node (ref "TSOC") (pin "7C") (pinfunction "RXD_7C") (pintype "bidirectional"))
    )
    (net (code "56") (name "TSOC_TXD") (class "Default")
      (node (ref "J7") (pin "1") (pinfunction "1_1") (pintype "passive"))
      (node (ref "J9") (pin "1") (pinfunction "1_1") (pintype "passive"))
      (node (ref "TSOC") (pin "8C") (pinfunction "TXD_8C") (pintype "bidirectional"))
    )
    (net (code "57") (name "VCC") (class "Default")
      (node (ref "C2") (pin "1") (pinfunction "1_1") (pintype "passive"))
      (node (ref "C3") (pin "2") (pinfunction "2_2") (pintype "passive"))
      (node (ref "C5") (pin "2") (pinfunction "2_2") (pintype "passive"))
      (node (ref "C9") (pin "1") (pinfunction "1_1") (pintype "passive"))
      (node (ref "J1") (pin "2") (pinfunction "2_2") (pintype "passive"))
      (node (ref "J14") (pin "11") (pinfunction "11_11") (pintype "passive"))
      (node (ref "J14") (pin "12") (pinfunction "12_12") (pintype "passive"))
      (node (ref "LED_B") (pin "A") (pinfunction "A_A") (pintype "passive"))
      (node (ref "LED_G") (pin "A") (pinfunction "A_A") (pintype "passive"))
      (node (ref "LED_R") (pin "A") (pinfunction "A_A") (pintype "passive"))
      (node (ref "LED_Y") (pin "A") (pinfunction "A_A") (pintype "passive"))
      (node (ref "R11") (pin "1") (pinfunction "1_1") (pintype "passive"))
      (node (ref "R22") (pin "1") (pinfunction "1_1") (pintype "passive"))
      (node (ref "R23") (pin "1") (pinfunction "1_1") (pintype "passive"))
      (node (ref "R3") (pin "2") (pinfunction "2_2") (pintype "passive"))
      (node (ref "R8") (pin "2") (pinfunction "2_2") (pintype "passive"))
      (node (ref "TSOC") (pin "6E") (pinfunction "VTARG_6E") (pintype "bidirectional"))
      (node (ref "U1") (pin "8") (pinfunction "VCC_8") (pintype "bidirectional"))
      (node (ref "U2") (pin "18") (pinfunction "AVCC_18") (pintype "bidirectional"))
      (node (ref "U2") (pin "19") (pinfunction "ADC6_19") (pintype "bidirectional"))
      (node (ref "U2") (pin "4") (pinfunction "VCC_4") (pintype "bidirectional"))
      (node (ref "U2") (pin "6") (pinfunction "VCC_6") (pintype "bidirectional"))
    )
    (net (code "58") (name "unconnected-(TSOC-JTDO-Pad2E)") (class "Default")
      (node (ref "TSOC") (pin "2E") (pinfunction "JTDO_2E") (pintype "bidirectional"))
    )
    (net (code "59") (name "unconnected-(TSOC-~{JDBG}-Pad1E)") (class "Default")
      (node (ref "TSOC") (pin "1E") (pinfunction "~{JDBG}_1E") (pintype "bidirectional"))
    )
  )
)
